# axiom_beta_plugin_module_1xHDMI_v0_5_2bc.net
KiCad netlist of a schematic drawn in EAGLE
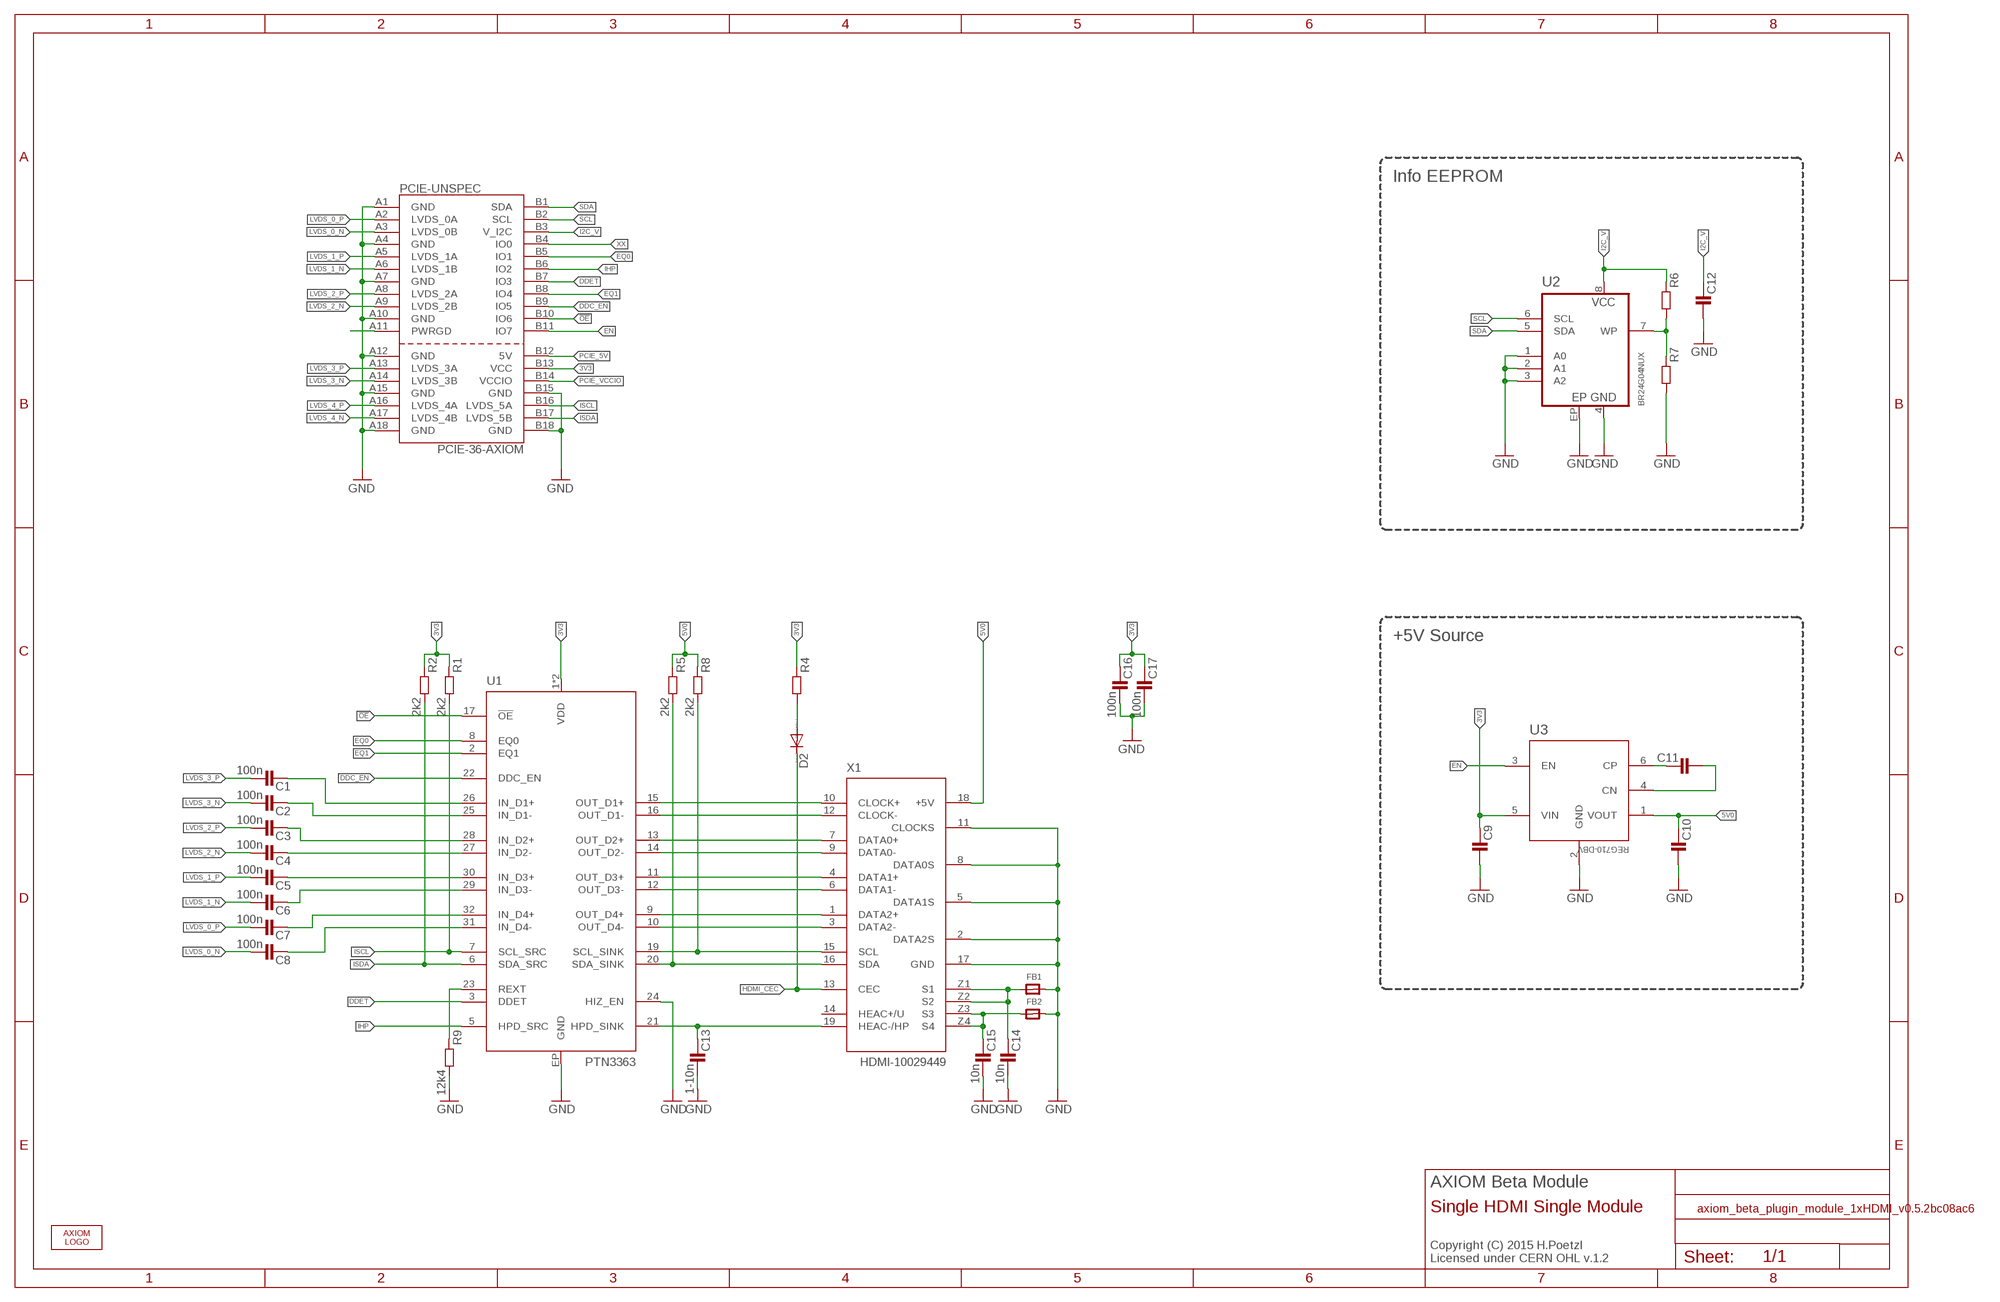
[diagram p0: schematic, sheet 1]

(export (version "E")
  (design (tool "Eeschema 10.0.6"))
  (components
    (comp (ref "C1")
      (value "100n")
      (footprint "eagle-import:0402-C")
      (libsource (lib "eagle-import") (part "C0402-C"))
    )
    (comp (ref "C2")
      (value "100n")
      (footprint "eagle-import:0402-C")
      (libsource (lib "eagle-import") (part "C0402-C"))
    )
    (comp (ref "C3")
      (value "100n")
      (footprint "eagle-import:0402-C")
      (libsource (lib "eagle-import") (part "C0402-C"))
    )
    (comp (ref "C4")
      (value "100n")
      (footprint "eagle-import:0402-C")
      (libsource (lib "eagle-import") (part "C0402-C"))
    )
    (comp (ref "C5")
      (value "100n")
      (footprint "eagle-import:0402-C")
      (libsource (lib "eagle-import") (part "C0402-C"))
    )
    (comp (ref "C6")
      (value "100n")
      (footprint "eagle-import:0402-C")
      (libsource (lib "eagle-import") (part "C0402-C"))
    )
    (comp (ref "C7")
      (value "100n")
      (footprint "eagle-import:0402-C")
      (libsource (lib "eagle-import") (part "C0402-C"))
    )
    (comp (ref "C8")
      (value "100n")
      (footprint "eagle-import:0402-C")
      (libsource (lib "eagle-import") (part "C0402-C"))
    )
    (comp (ref "C9")
      (value "C0603-B")
      (footprint "eagle-import:0603-B")
      (libsource (lib "eagle-import") (part "C0603-B"))
    )
    (comp (ref "C10")
      (value "C0603-B")
      (footprint "eagle-import:0603-B")
      (libsource (lib "eagle-import") (part "C0603-B"))
    )
    (comp (ref "C11")
      (value "C0603-B")
      (footprint "eagle-import:0603-B")
      (libsource (lib "eagle-import") (part "C0603-B"))
    )
    (comp (ref "C12")
      (value "C0402-B")
      (footprint "eagle-import:0402-B")
      (libsource (lib "eagle-import") (part "C0402-B"))
    )
    (comp (ref "C13")
      (value "1-10n")
      (footprint "eagle-import:0402-B")
      (libsource (lib "eagle-import") (part "C0402-B"))
    )
    (comp (ref "C14")
      (value "10n")
      (footprint "eagle-import:0402-B")
      (libsource (lib "eagle-import") (part "C0402-B"))
    )
    (comp (ref "C15")
      (value "10n")
      (footprint "eagle-import:0402-B")
      (libsource (lib "eagle-import") (part "C0402-B"))
    )
    (comp (ref "C16")
      (value "100n")
      (footprint "eagle-import:0402-B")
      (libsource (lib "eagle-import") (part "C0402-B"))
    )
    (comp (ref "C17")
      (value "100n")
      (footprint "eagle-import:0402-B")
      (libsource (lib "eagle-import") (part "C0402-B"))
    )
    (comp (ref "D2")
      (value "DIODE-SOD523")
      (footprint "eagle-import:SOD523")
      (libsource (lib "eagle-import") (part "DIODE-SOD523"))
    )
    (comp (ref "FB1")
      (value "FERRITE_0603MP")
      (footprint "eagle-import:_0603MP")
      (libsource (lib "eagle-import") (part "FERRITE_0603MP"))
    )
    (comp (ref "FB2")
      (value "FERRITE_0603MP")
      (footprint "eagle-import:_0603MP")
      (libsource (lib "eagle-import") (part "FERRITE_0603MP"))
    )
    (comp (ref "PCIE-UNSPEC")
      (value "PCIE-36-AXIOM")
      (footprint "eagle-import:PCIE-36-AXIOM")
      (libsource (lib "eagle-import") (part "PCIE-36-AXIOM"))
    )
    (comp (ref "R1")
      (value "2k2")
      (footprint "eagle-import:0402-B")
      (libsource (lib "eagle-import") (part "R0402-B"))
    )
    (comp (ref "R2")
      (value "2k2")
      (footprint "eagle-import:0402-B")
      (libsource (lib "eagle-import") (part "R0402-B"))
    )
    (comp (ref "R4")
      (value "R0402-B")
      (footprint "eagle-import:0402-B")
      (libsource (lib "eagle-import") (part "R0402-B"))
    )
    (comp (ref "R5")
      (value "2k2")
      (footprint "eagle-import:0402-B")
      (libsource (lib "eagle-import") (part "R0402-B"))
    )
    (comp (ref "R6")
      (value "R0402-B")
      (footprint "eagle-import:0402-B")
      (libsource (lib "eagle-import") (part "R0402-B"))
    )
    (comp (ref "R7")
      (value "R0402-B")
      (footprint "eagle-import:0402-B")
      (libsource (lib "eagle-import") (part "R0402-B"))
    )
    (comp (ref "R8")
      (value "2k2")
      (footprint "eagle-import:0402-B")
      (libsource (lib "eagle-import") (part "R0402-B"))
    )
    (comp (ref "R9")
      (value "12k4")
      (footprint "eagle-import:0402-B")
      (libsource (lib "eagle-import") (part "R0402-B"))
    )
    (comp (ref "U$1")
      (value "AXIOM_LOGO459X70")
      (footprint "eagle-import:AXIOM_LOGO_459X70")
      (libsource (lib "eagle-import") (part "AXIOM_LOGO459X70"))
    )
    (comp (ref "U1")
      (value "PTN3363")
      (footprint "eagle-import:HVQFN32")
      (libsource (lib "eagle-import") (part "PTN3363"))
    )
    (comp (ref "U2")
      (value "BR24G04NUX")
      (footprint "eagle-import:DFN200X300X100-9N")
      (libsource (lib "eagle-import") (part "BR24G04NUX"))
    )
    (comp (ref "U3")
      (value "REG710-DBV")
      (footprint "eagle-import:DBV")
      (libsource (lib "eagle-import") (part "REG710-DBV"))
    )
    (comp (ref "X1")
      (value "HDMI-10029449")
      (footprint "eagle-import:10029449-X01XLF")
      (libsource (lib "eagle-import") (part "HDMI-10029449"))
    )
  )
  (nets
    (net (code "1") (name "/~{OE}") (class "Default")
      (node (ref "PCIE-UNSPEC") (pin "B10") (pinfunction "IO6_B10") (pintype "passive"))
      (node (ref "U1") (pin "17") (pinfunction "~{OE}_17") (pintype "bidirectional"))
    )
    (net (code "2") (name "3V3") (class "Default")
      (node (ref "C16") (pin "1") (pinfunction "1_1") (pintype "passive"))
      (node (ref "C17") (pin "1") (pinfunction "1_1") (pintype "passive"))
      (node (ref "C9") (pin "1") (pinfunction "1_1") (pintype "passive"))
      (node (ref "PCIE-UNSPEC") (pin "B13") (pinfunction "VCC_B13") (pintype "passive"))
      (node (ref "R1") (pin "1") (pinfunction "1_1") (pintype "passive"))
      (node (ref "R2") (pin "1") (pinfunction "1_1") (pintype "passive"))
      (node (ref "R4") (pin "1") (pinfunction "1_1") (pintype "passive"))
      (node (ref "U1") (pin "1") (pinfunction "VDD_1") (pintype "power_in"))
      (node (ref "U1") (pin "18") (pinfunction "VDD_18") (pintype "power_in"))
      (node (ref "U3") (pin "5") (pinfunction "VIN_5") (pintype "power_in"))
    )
    (net (code "3") (name "5V0") (class "Default")
      (node (ref "C10") (pin "1") (pinfunction "1_1") (pintype "passive"))
      (node (ref "R5") (pin "1") (pinfunction "1_1") (pintype "passive"))
      (node (ref "R8") (pin "1") (pinfunction "1_1") (pintype "passive"))
      (node (ref "U3") (pin "1") (pinfunction "VOUT_1") (pintype "output"))
      (node (ref "X1") (pin "18") (pinfunction "+5V_18") (pintype "power_in"))
    )
    (net (code "4") (name "DDC_EN") (class "Default")
      (node (ref "PCIE-UNSPEC") (pin "B9") (pinfunction "IO5_B9") (pintype "passive"))
      (node (ref "U1") (pin "22") (pinfunction "DDC_EN_22") (pintype "bidirectional"))
    )
    (net (code "5") (name "DDET") (class "Default")
      (node (ref "PCIE-UNSPEC") (pin "B7") (pinfunction "IO3_B7") (pintype "passive"))
      (node (ref "U1") (pin "3") (pinfunction "DDET_3") (pintype "bidirectional"))
    )
    (net (code "6") (name "EN") (class "Default")
      (node (ref "PCIE-UNSPEC") (pin "B11") (pinfunction "IO7_B11") (pintype "passive"))
      (node (ref "U3") (pin "3") (pinfunction "EN_3") (pintype "input"))
    )
    (net (code "7") (name "EQ0") (class "Default")
      (node (ref "PCIE-UNSPEC") (pin "B5") (pinfunction "IO1_B5") (pintype "passive"))
      (node (ref "U1") (pin "8") (pinfunction "EQ0_8") (pintype "bidirectional"))
    )
    (net (code "8") (name "EQ1") (class "Default")
      (node (ref "PCIE-UNSPEC") (pin "B8") (pinfunction "IO4_B8") (pintype "passive"))
      (node (ref "U1") (pin "2") (pinfunction "EQ1_2") (pintype "bidirectional"))
    )
    (net (code "9") (name "GND") (class "Default")
      (node (ref "C10") (pin "2") (pinfunction "2_2") (pintype "passive"))
      (node (ref "C12") (pin "2") (pinfunction "2_2") (pintype "passive"))
      (node (ref "C13") (pin "2") (pinfunction "2_2") (pintype "passive"))
      (node (ref "C14") (pin "2") (pinfunction "2_2") (pintype "passive"))
      (node (ref "C15") (pin "2") (pinfunction "2_2") (pintype "passive"))
      (node (ref "C16") (pin "2") (pinfunction "2_2") (pintype "passive"))
      (node (ref "C17") (pin "2") (pinfunction "2_2") (pintype "passive"))
      (node (ref "C9") (pin "2") (pinfunction "2_2") (pintype "passive"))
      (node (ref "FB1") (pin "2") (pinfunction "P$2_2") (pintype "passive"))
      (node (ref "FB2") (pin "2") (pinfunction "P$2_2") (pintype "passive"))
      (node (ref "PCIE-UNSPEC") (pin "A1") (pinfunction "GND_A1") (pintype "passive"))
      (node (ref "PCIE-UNSPEC") (pin "A10") (pinfunction "GND_A10") (pintype "passive"))
      (node (ref "PCIE-UNSPEC") (pin "A12") (pinfunction "GND_A12") (pintype "passive"))
      (node (ref "PCIE-UNSPEC") (pin "A15") (pinfunction "GND_A15") (pintype "passive"))
      (node (ref "PCIE-UNSPEC") (pin "A18") (pinfunction "GND_A18") (pintype "passive"))
      (node (ref "PCIE-UNSPEC") (pin "A4") (pinfunction "GND_A4") (pintype "passive"))
      (node (ref "PCIE-UNSPEC") (pin "A7") (pinfunction "GND_A7") (pintype "passive"))
      (node (ref "PCIE-UNSPEC") (pin "B15") (pinfunction "GND_B15") (pintype "passive"))
      (node (ref "PCIE-UNSPEC") (pin "B18") (pinfunction "GND_B18") (pintype "passive"))
      (node (ref "R7") (pin "2") (pinfunction "2_2") (pintype "passive"))
      (node (ref "R9") (pin "2") (pinfunction "2_2") (pintype "passive"))
      (node (ref "U1") (pin "24") (pinfunction "HIZ_EN_24") (pintype "bidirectional"))
      (node (ref "U1") (pin "EP") (pinfunction "GND_EP") (pintype "bidirectional"))
      (node (ref "U2") (pin "1") (pinfunction "A0_1") (pintype "input"))
      (node (ref "U2") (pin "2") (pinfunction "A1_2") (pintype "input"))
      (node (ref "U2") (pin "3") (pinfunction "A2_3") (pintype "input"))
      (node (ref "U2") (pin "4") (pinfunction "GND_4") (pintype "passive"))
      (node (ref "U2") (pin "EP") (pinfunction "EP_EP") (pintype "passive"))
      (node (ref "U3") (pin "2") (pinfunction "GND_2") (pintype "passive"))
      (node (ref "X1") (pin "11") (pinfunction "CLOCKS_11") (pintype "power_in"))
      (node (ref "X1") (pin "17") (pinfunction "GND_17") (pintype "bidirectional"))
      (node (ref "X1") (pin "2") (pinfunction "DATA2S_2") (pintype "power_in"))
      (node (ref "X1") (pin "5") (pinfunction "DATA1S_5") (pintype "power_in"))
      (node (ref "X1") (pin "8") (pinfunction "DATA0S_8") (pintype "power_in"))
    )
    (net (code "10") (name "HDMI_CEC") (class "Default")
      (node (ref "D2") (pin "C") (pinfunction "C_C") (pintype "passive"))
      (node (ref "X1") (pin "13") (pinfunction "CEC_13") (pintype "bidirectional"))
    )
    (net (code "11") (name "I2C_V") (class "Default")
      (node (ref "C12") (pin "1") (pinfunction "1_1") (pintype "passive"))
      (node (ref "PCIE-UNSPEC") (pin "B3") (pinfunction "V_I2C_B3") (pintype "passive"))
      (node (ref "R6") (pin "1") (pinfunction "1_1") (pintype "passive"))
      (node (ref "U2") (pin "8") (pinfunction "VCC_8") (pintype "power_in"))
    )
    (net (code "12") (name "IHP") (class "Default")
      (node (ref "PCIE-UNSPEC") (pin "B6") (pinfunction "IO2_B6") (pintype "passive"))
      (node (ref "U1") (pin "5") (pinfunction "HPD_SRC_5") (pintype "bidirectional"))
    )
    (net (code "13") (name "ISCL") (class "Default")
      (node (ref "PCIE-UNSPEC") (pin "B16") (pinfunction "LVDS_5A_B16") (pintype "passive"))
      (node (ref "R1") (pin "2") (pinfunction "2_2") (pintype "passive"))
      (node (ref "U1") (pin "7") (pinfunction "SCL_SRC_7") (pintype "bidirectional"))
    )
    (net (code "14") (name "ISDA") (class "Default")
      (node (ref "PCIE-UNSPEC") (pin "B17") (pinfunction "LVDS_5B_B17") (pintype "passive"))
      (node (ref "R2") (pin "2") (pinfunction "2_2") (pintype "passive"))
      (node (ref "U1") (pin "6") (pinfunction "SDA_SRC_6") (pintype "bidirectional"))
    )
    (net (code "15") (name "LVDS_0_N") (class "Default")
      (node (ref "C8") (pin "2") (pinfunction "2_2") (pintype "passive"))
      (node (ref "PCIE-UNSPEC") (pin "A3") (pinfunction "LVDS_0B_A3") (pintype "passive"))
    )
    (net (code "16") (name "LVDS_0_P") (class "Default")
      (node (ref "C7") (pin "2") (pinfunction "2_2") (pintype "passive"))
      (node (ref "PCIE-UNSPEC") (pin "A2") (pinfunction "LVDS_0A_A2") (pintype "passive"))
    )
    (net (code "17") (name "LVDS_1_N") (class "Default")
      (node (ref "C6") (pin "2") (pinfunction "2_2") (pintype "passive"))
      (node (ref "PCIE-UNSPEC") (pin "A6") (pinfunction "LVDS_1B_A6") (pintype "passive"))
    )
    (net (code "18") (name "LVDS_1_P") (class "Default")
      (node (ref "C5") (pin "2") (pinfunction "2_2") (pintype "passive"))
      (node (ref "PCIE-UNSPEC") (pin "A5") (pinfunction "LVDS_1A_A5") (pintype "passive"))
    )
    (net (code "19") (name "LVDS_2_N") (class "Default")
      (node (ref "C4") (pin "2") (pinfunction "2_2") (pintype "passive"))
      (node (ref "PCIE-UNSPEC") (pin "A9") (pinfunction "LVDS_2B_A9") (pintype "passive"))
    )
    (net (code "20") (name "LVDS_2_P") (class "Default")
      (node (ref "C3") (pin "2") (pinfunction "2_2") (pintype "passive"))
      (node (ref "PCIE-UNSPEC") (pin "A8") (pinfunction "LVDS_2A_A8") (pintype "passive"))
    )
    (net (code "21") (name "LVDS_3_N") (class "Default")
      (node (ref "C2") (pin "2") (pinfunction "2_2") (pintype "passive"))
      (node (ref "PCIE-UNSPEC") (pin "A14") (pinfunction "LVDS_3B_A14") (pintype "passive"))
    )
    (net (code "22") (name "LVDS_3_P") (class "Default")
      (node (ref "C1") (pin "2") (pinfunction "2_2") (pintype "passive"))
      (node (ref "PCIE-UNSPEC") (pin "A13") (pinfunction "LVDS_3A_A13") (pintype "passive"))
    )
    (net (code "23") (name "LVDS_4_N") (class "Default")
      (node (ref "PCIE-UNSPEC") (pin "A17") (pinfunction "LVDS_4B_A17") (pintype "passive"))
    )
    (net (code "24") (name "LVDS_4_P") (class "Default")
      (node (ref "PCIE-UNSPEC") (pin "A16") (pinfunction "LVDS_4A_A16") (pintype "passive"))
    )
    (net (code "25") (name "Net-(D2-PadA)") (class "Default")
      (node (ref "D2") (pin "A") (pinfunction "A_A") (pintype "passive"))
      (node (ref "R4") (pin "2") (pinfunction "2_2") (pintype "passive"))
    )
    (net (code "26") (name "Net-(FB1-P$1)") (class "Default")
      (node (ref "C14") (pin "1") (pinfunction "1_1") (pintype "passive"))
      (node (ref "FB1") (pin "1") (pinfunction "P$1_1") (pintype "passive"))
      (node (ref "X1") (pin "Z1") (pinfunction "S1_Z1") (pintype "power_in"))
      (node (ref "X1") (pin "Z2") (pinfunction "S2_Z2") (pintype "power_in"))
    )
    (net (code "27") (name "Net-(FB2-P$1)") (class "Default")
      (node (ref "C15") (pin "1") (pinfunction "1_1") (pintype "passive"))
      (node (ref "FB2") (pin "1") (pinfunction "P$1_1") (pintype "passive"))
      (node (ref "X1") (pin "Z3") (pinfunction "S3_Z3") (pintype "power_in"))
      (node (ref "X1") (pin "Z4") (pinfunction "S4_Z4") (pintype "power_in"))
    )
    (net (code "28") (name "Net-(U1-HPD_SINK)") (class "Default")
      (node (ref "C13") (pin "1") (pinfunction "1_1") (pintype "passive"))
      (node (ref "U1") (pin "21") (pinfunction "HPD_SINK_21") (pintype "bidirectional"))
      (node (ref "X1") (pin "19") (pinfunction "HEAC-/HP_19") (pintype "bidirectional"))
    )
    (net (code "29") (name "Net-(U1-IN_D1+)") (class "Default")
      (node (ref "C1") (pin "1") (pinfunction "1_1") (pintype "passive"))
      (node (ref "U1") (pin "26") (pinfunction "IN_D1+_26") (pintype "bidirectional"))
    )
    (net (code "30") (name "Net-(U1-IN_D1-)") (class "Default")
      (node (ref "C2") (pin "1") (pinfunction "1_1") (pintype "passive"))
      (node (ref "U1") (pin "25") (pinfunction "IN_D1-_25") (pintype "bidirectional"))
    )
    (net (code "31") (name "Net-(U1-IN_D2+)") (class "Default")
      (node (ref "C3") (pin "1") (pinfunction "1_1") (pintype "passive"))
      (node (ref "U1") (pin "28") (pinfunction "IN_D2+_28") (pintype "bidirectional"))
    )
    (net (code "32") (name "Net-(U1-IN_D2-)") (class "Default")
      (node (ref "C4") (pin "1") (pinfunction "1_1") (pintype "passive"))
      (node (ref "U1") (pin "27") (pinfunction "IN_D2-_27") (pintype "bidirectional"))
    )
    (net (code "33") (name "Net-(U1-IN_D3+)") (class "Default")
      (node (ref "C5") (pin "1") (pinfunction "1_1") (pintype "passive"))
      (node (ref "U1") (pin "30") (pinfunction "IN_D3+_30") (pintype "bidirectional"))
    )
    (net (code "34") (name "Net-(U1-IN_D3-)") (class "Default")
      (node (ref "C6") (pin "1") (pinfunction "1_1") (pintype "passive"))
      (node (ref "U1") (pin "29") (pinfunction "IN_D3-_29") (pintype "bidirectional"))
    )
    (net (code "35") (name "Net-(U1-IN_D4+)") (class "Default")
      (node (ref "C7") (pin "1") (pinfunction "1_1") (pintype "passive"))
      (node (ref "U1") (pin "32") (pinfunction "IN_D4+_32") (pintype "bidirectional"))
    )
    (net (code "36") (name "Net-(U1-IN_D4-)") (class "Default")
      (node (ref "C8") (pin "1") (pinfunction "1_1") (pintype "passive"))
      (node (ref "U1") (pin "31") (pinfunction "IN_D4-_31") (pintype "bidirectional"))
    )
    (net (code "37") (name "Net-(U1-OUT_D1+)") (class "Default")
      (node (ref "U1") (pin "15") (pinfunction "OUT_D1+_15") (pintype "bidirectional"))
      (node (ref "X1") (pin "10") (pinfunction "CLOCK+_10") (pintype "bidirectional"))
    )
    (net (code "38") (name "Net-(U1-OUT_D1-)") (class "Default")
      (node (ref "U1") (pin "16") (pinfunction "OUT_D1-_16") (pintype "bidirectional"))
      (node (ref "X1") (pin "12") (pinfunction "CLOCK-_12") (pintype "bidirectional"))
    )
    (net (code "39") (name "Net-(U1-OUT_D2+)") (class "Default")
      (node (ref "U1") (pin "13") (pinfunction "OUT_D2+_13") (pintype "bidirectional"))
      (node (ref "X1") (pin "7") (pinfunction "DATA0+_7") (pintype "bidirectional"))
    )
    (net (code "40") (name "Net-(U1-OUT_D2-)") (class "Default")
      (node (ref "U1") (pin "14") (pinfunction "OUT_D2-_14") (pintype "bidirectional"))
      (node (ref "X1") (pin "9") (pinfunction "DATA0-_9") (pintype "bidirectional"))
    )
    (net (code "41") (name "Net-(U1-OUT_D3+)") (class "Default")
      (node (ref "U1") (pin "11") (pinfunction "OUT_D3+_11") (pintype "bidirectional"))
      (node (ref "X1") (pin "4") (pinfunction "DATA1+_4") (pintype "bidirectional"))
    )
    (net (code "42") (name "Net-(U1-OUT_D3-)") (class "Default")
      (node (ref "U1") (pin "12") (pinfunction "OUT_D3-_12") (pintype "bidirectional"))
      (node (ref "X1") (pin "6") (pinfunction "DATA1-_6") (pintype "bidirectional"))
    )
    (net (code "43") (name "Net-(U1-OUT_D4+)") (class "Default")
      (node (ref "U1") (pin "9") (pinfunction "OUT_D4+_9") (pintype "bidirectional"))
      (node (ref "X1") (pin "1") (pinfunction "DATA2+_1") (pintype "bidirectional"))
    )
    (net (code "44") (name "Net-(U1-OUT_D4-)") (class "Default")
      (node (ref "U1") (pin "10") (pinfunction "OUT_D4-_10") (pintype "bidirectional"))
      (node (ref "X1") (pin "3") (pinfunction "DATA2-_3") (pintype "bidirectional"))
    )
    (net (code "45") (name "Net-(U1-REXT)") (class "Default")
      (node (ref "R9") (pin "1") (pinfunction "1_1") (pintype "passive"))
      (node (ref "U1") (pin "23") (pinfunction "REXT_23") (pintype "bidirectional"))
    )
    (net (code "46") (name "Net-(U1-SCL_SINK)") (class "Default")
      (node (ref "R8") (pin "2") (pinfunction "2_2") (pintype "passive"))
      (node (ref "U1") (pin "19") (pinfunction "SCL_SINK_19") (pintype "bidirectional"))
      (node (ref "X1") (pin "15") (pinfunction "SCL_15") (pintype "bidirectional"))
    )
    (net (code "47") (name "Net-(U1-SDA_SINK)") (class "Default")
      (node (ref "R5") (pin "2") (pinfunction "2_2") (pintype "passive"))
      (node (ref "U1") (pin "20") (pinfunction "SDA_SINK_20") (pintype "bidirectional"))
      (node (ref "X1") (pin "16") (pinfunction "SDA_16") (pintype "bidirectional"))
    )
    (net (code "48") (name "Net-(U2-WP)") (class "Default")
      (node (ref "R6") (pin "2") (pinfunction "2_2") (pintype "passive"))
      (node (ref "R7") (pin "1") (pinfunction "1_1") (pintype "passive"))
      (node (ref "U2") (pin "7") (pinfunction "WP_7") (pintype "input"))
    )
    (net (code "49") (name "Net-(U3-CN)") (class "Default")
      (node (ref "C11") (pin "2") (pinfunction "2_2") (pintype "passive"))
      (node (ref "U3") (pin "4") (pinfunction "CN_4") (pintype "power_in"))
    )
    (net (code "50") (name "Net-(U3-CP)") (class "Default")
      (node (ref "C11") (pin "1") (pinfunction "1_1") (pintype "passive"))
      (node (ref "U3") (pin "6") (pinfunction "CP_6") (pintype "output"))
    )
    (net (code "51") (name "PCIE_5V") (class "Default")
      (node (ref "PCIE-UNSPEC") (pin "B12") (pinfunction "5V_B12") (pintype "passive"))
    )
    (net (code "52") (name "PCIE_VCCIO") (class "Default")
      (node (ref "PCIE-UNSPEC") (pin "B14") (pinfunction "VCCIO_B14") (pintype "passive"))
    )
    (net (code "53") (name "SCL") (class "Default")
      (node (ref "PCIE-UNSPEC") (pin "B2") (pinfunction "SCL_B2") (pintype "passive"))
      (node (ref "U2") (pin "6") (pinfunction "SCL_6") (pintype "input"))
    )
    (net (code "54") (name "SDA") (class "Default")
      (node (ref "PCIE-UNSPEC") (pin "B1") (pinfunction "SDA_B1") (pintype "passive"))
      (node (ref "U2") (pin "5") (pinfunction "SDA_5") (pintype "bidirectional"))
    )
    (net (code "55") (name "XX") (class "Default")
      (node (ref "PCIE-UNSPEC") (pin "B4") (pinfunction "IO0_B4") (pintype "passive"))
    )
    (net (code "56") (name "unconnected-(PCIE-UNSPEC-PWRGD-PadA11)") (class "Default")
      (node (ref "PCIE-UNSPEC") (pin "A11") (pinfunction "PWRGD_A11") (pintype "passive"))
    )
    (net (code "57") (name "unconnected-(X1-HEAC+{slash}U-Pad14)") (class "Default")
      (node (ref "X1") (pin "14") (pinfunction "HEAC+/U_14") (pintype "bidirectional"))
    )
  )
)
